# oresat0-plusz-end-cap.net
KiCad netlist of a schematic drawn in EAGLE
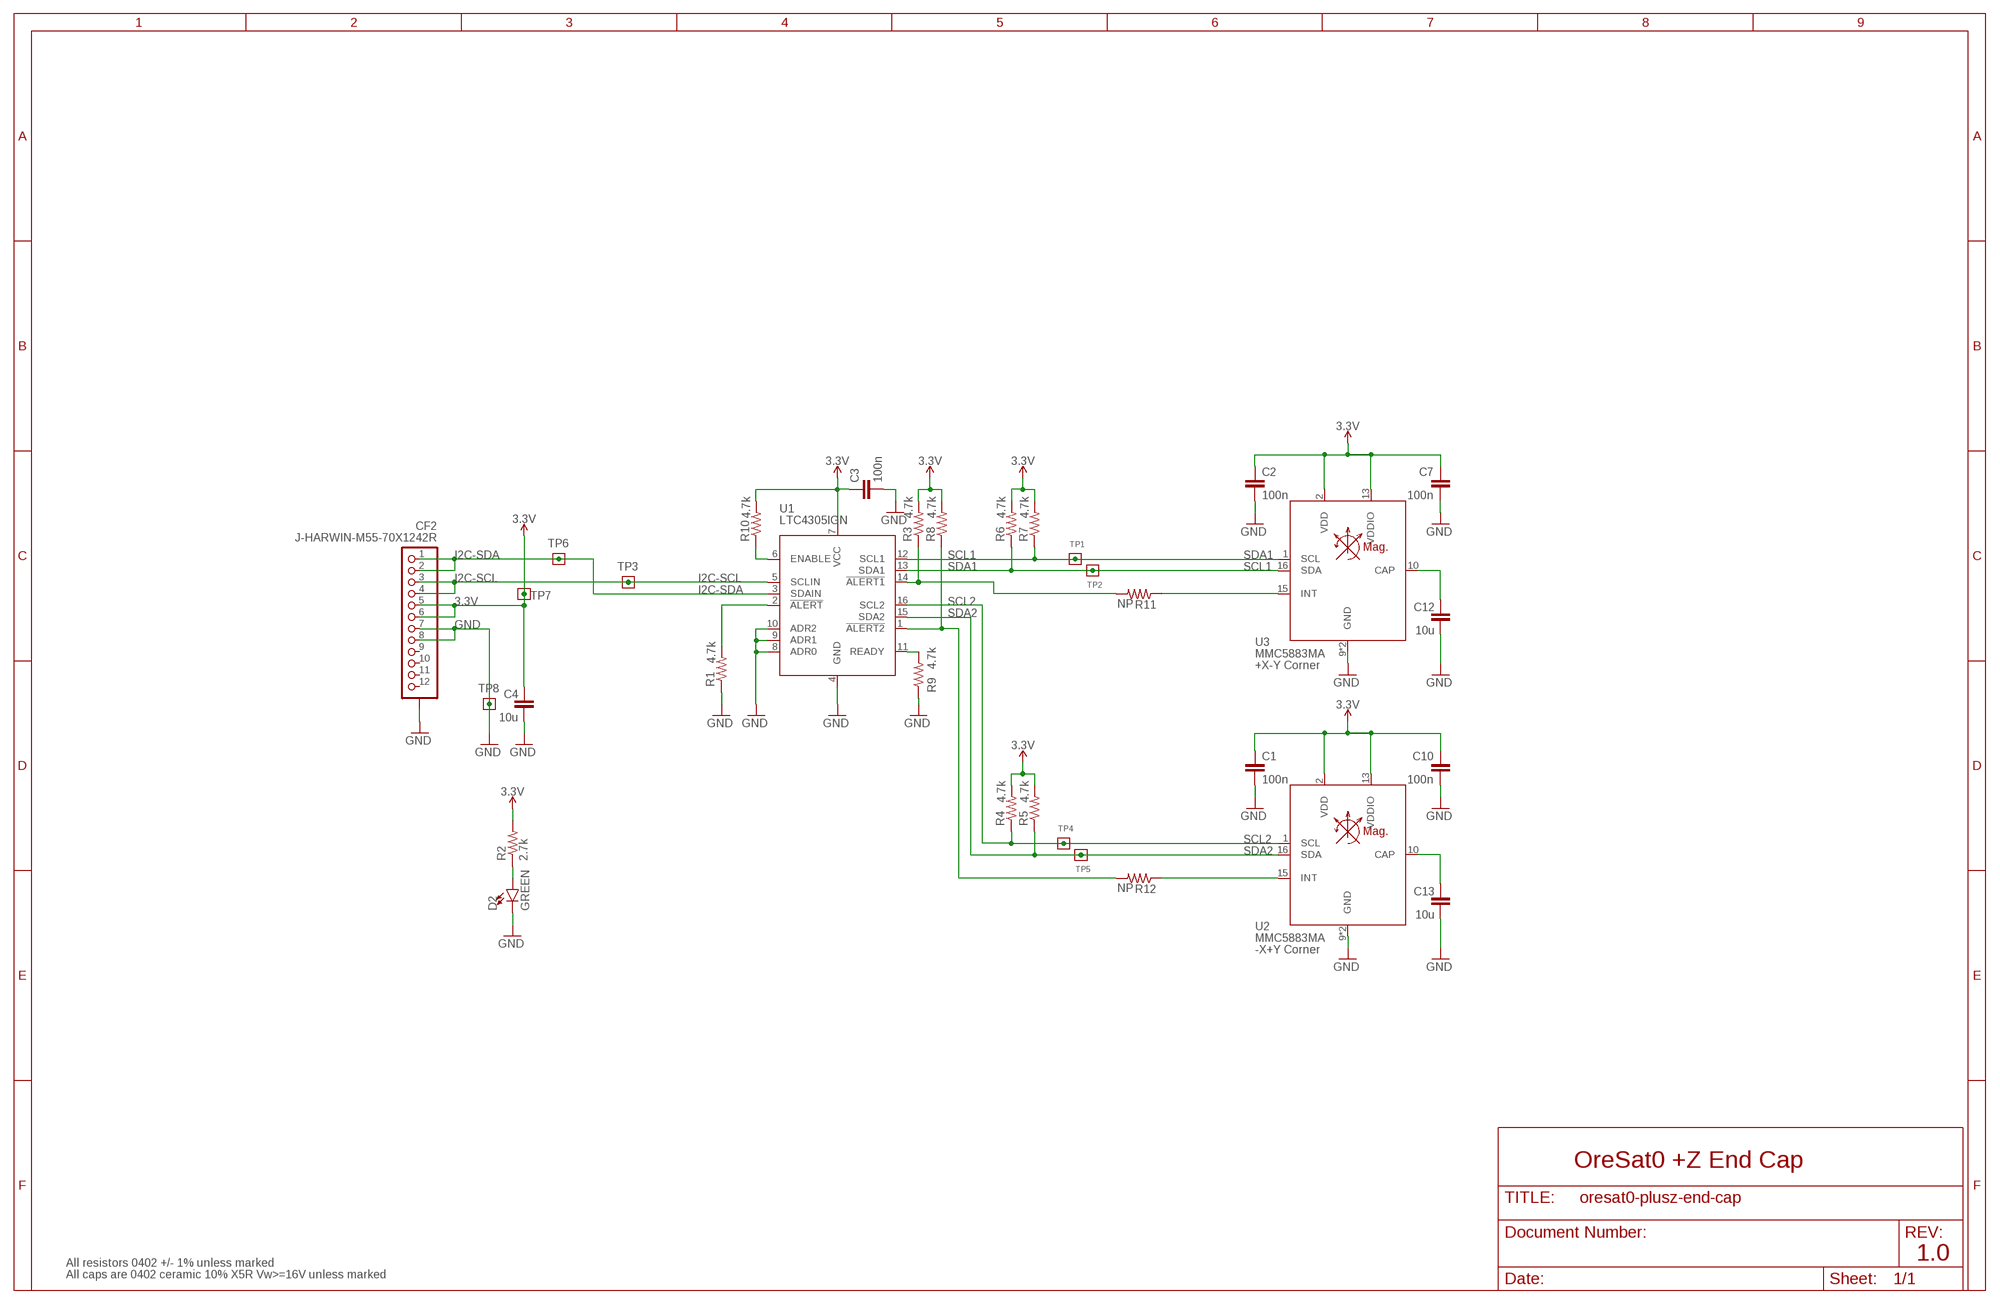
[diagram p0: schematic, sheet 1]

(export (version "E")
  (design (tool "Eeschema 10.0.6"))
  (components
    (comp (ref "C1")
      (value "100n")
      (footprint "eagle-import:.0603-B-NOSILK")
      (fields (field (name "MFR") "Samsung") (field (name "MPN") "CL10B104KB8NNNL"))
      (libsource (lib "eagle-import") (part "C-EU0603-B-NOSILK"))
    )
    (comp (ref "C2")
      (value "100n")
      (footprint "eagle-import:.0603-B-NOSILK")
      (fields (field (name "MFR") "Samsung") (field (name "MPN") "CL10B104KB8NNNL"))
      (libsource (lib "eagle-import") (part "C-EU0603-B-NOSILK"))
    )
    (comp (ref "C3")
      (value "100n")
      (footprint "eagle-import:.0603-B-NOSILK")
      (fields (field (name "MFR") "Samsung") (field (name "MPN") "CL10B104KB8NNNL"))
      (libsource (lib "eagle-import") (part "C-EU0603-B-NOSILK"))
    )
    (comp (ref "C4")
      (value "10u")
      (footprint "eagle-import:.0603-B-NOSILK")
      (fields (field (name "MFR") "Murata") (field (name "MPN") "GRM188D71A106KA73D"))
      (libsource (lib "eagle-import") (part "C-EU0603-B-NOSILK"))
    )
    (comp (ref "C7")
      (value "100n")
      (footprint "eagle-import:.0603-B-NOSILK")
      (fields (field (name "MFR") "Samsung") (field (name "MPN") "CL10B104KB8NNNL"))
      (libsource (lib "eagle-import") (part "C-EU0603-B-NOSILK"))
    )
    (comp (ref "C10")
      (value "100n")
      (footprint "eagle-import:.0603-B-NOSILK")
      (fields (field (name "MFR") "Samsung") (field (name "MPN") "CL10B104KB8NNNL"))
      (libsource (lib "eagle-import") (part "C-EU0603-B-NOSILK"))
    )
    (comp (ref "C12")
      (value "10u")
      (footprint "eagle-import:.0603-B-NOSILK")
      (fields (field (name "MFR") "Murata") (field (name "MPN") "GRM188D71A106KA73D"))
      (libsource (lib "eagle-import") (part "C-EU0603-B-NOSILK"))
    )
    (comp (ref "C13")
      (value "10u")
      (footprint "eagle-import:.0603-B-NOSILK")
      (fields (field (name "MFR") "Murata") (field (name "MPN") "GRM188D71A106KA73D"))
      (libsource (lib "eagle-import") (part "C-EU0603-B-NOSILK"))
    )
    (comp (ref "CF2")
      (value "J-HARWIN-M55-70X1242R")
      (footprint "eagle-import:HARWIN-M55-70X1242R")
      (fields (field (name "MFR") "Harwin") (field (name "MPN") "M55-7011242R"))
      (libsource (lib "eagle-import") (part "J-HARWIN-M55-70X1242R"))
    )
    (comp (ref "D2")
      (value "GREEN")
      (footprint "eagle-import:LED-0603")
      (fields (field (name "MFR") "Rohn") (field (name "MPN") "SML-E12M8WT86"))
      (libsource (lib "eagle-import") (part "LED-GREEN0603"))
    )
    (comp (ref "R1")
      (value "4.7k")
      (footprint "eagle-import:.0603-B-NOSILK")
      (fields (field (name "MFR") "TE Connectivity") (field (name "MPN") "CRGCQ0603F4K7"))
      (libsource (lib "eagle-import") (part "R-US_0603-B-NOSILK"))
    )
    (comp (ref "R2")
      (value "2.7k")
      (footprint "eagle-import:.0603-B-NOSILK")
      (fields (field (name "MFR") "TE Connectivity") (field (name "MPN") "CRGCQ0603F2K7"))
      (libsource (lib "eagle-import") (part "R-US_0603-B-NOSILK"))
    )
    (comp (ref "R3")
      (value "4.7k")
      (footprint "eagle-import:.0603-B-NOSILK")
      (fields (field (name "MFR") "TE Connectivity") (field (name "MPN") "CRGCQ0603F4K7"))
      (libsource (lib "eagle-import") (part "R-US_0603-B-NOSILK"))
    )
    (comp (ref "R4")
      (value "4.7k")
      (footprint "eagle-import:.0603-B-NOSILK")
      (fields (field (name "MFR") "TE Connectivity") (field (name "MPN") "CRGCQ0603F4K7"))
      (libsource (lib "eagle-import") (part "R-US_0603-B-NOSILK"))
    )
    (comp (ref "R5")
      (value "4.7k")
      (footprint "eagle-import:.0603-B-NOSILK")
      (fields (field (name "MFR") "TE Connectivity") (field (name "MPN") "CRGCQ0603F4K7"))
      (libsource (lib "eagle-import") (part "R-US_0603-B-NOSILK"))
    )
    (comp (ref "R6")
      (value "4.7k")
      (footprint "eagle-import:.0603-B-NOSILK")
      (fields (field (name "MFR") "TE Connectivity") (field (name "MPN") "CRGCQ0603F4K7"))
      (libsource (lib "eagle-import") (part "R-US_0603-B-NOSILK"))
    )
    (comp (ref "R7")
      (value "4.7k")
      (footprint "eagle-import:.0603-B-NOSILK")
      (fields (field (name "MFR") "TE Connectivity") (field (name "MPN") "CRGCQ0603F4K7"))
      (libsource (lib "eagle-import") (part "R-US_0603-B-NOSILK"))
    )
    (comp (ref "R8")
      (value "4.7k")
      (footprint "eagle-import:.0603-B-NOSILK")
      (fields (field (name "MFR") "TE Connectivity") (field (name "MPN") "CRGCQ0603F4K7"))
      (libsource (lib "eagle-import") (part "R-US_0603-B-NOSILK"))
    )
    (comp (ref "R9")
      (value "4.7k")
      (footprint "eagle-import:.0603-B-NOSILK")
      (fields (field (name "MFR") "TE Connectivity") (field (name "MPN") "CRGCQ0603F4K7"))
      (libsource (lib "eagle-import") (part "R-US_0603-B-NOSILK"))
    )
    (comp (ref "R10")
      (value "4.7k")
      (footprint "eagle-import:.0603-B-NOSILK")
      (fields (field (name "MFR") "TE Connectivity") (field (name "MPN") "CRGCQ0603F4K7"))
      (libsource (lib "eagle-import") (part "R-US_0603-B-NOSILK"))
    )
    (comp (ref "R11")
      (value "NP")
      (footprint "eagle-import:.0603-B-NOSILK")
      (libsource (lib "eagle-import") (part "R-US_0603-B-NOSILK"))
    )
    (comp (ref "R12")
      (value "NP")
      (footprint "eagle-import:.0603-B-NOSILK")
      (libsource (lib "eagle-import") (part "R-US_0603-B-NOSILK"))
    )
    (comp (ref "TP1")
      (value "TEST-POINT-LARGE-SQUARE")
      (footprint "eagle-import:1X01")
      (libsource (lib "eagle-import") (part "TEST-POINT-LARGE-SQUARE"))
    )
    (comp (ref "TP2")
      (value "TEST-POINT-LARGE-SQUARE")
      (footprint "eagle-import:1X01")
      (libsource (lib "eagle-import") (part "TEST-POINT-LARGE-SQUARE"))
    )
    (comp (ref "TP3")
      (value "TEST-POINT-LARGE-SQUARE")
      (footprint "eagle-import:1X01")
      (libsource (lib "eagle-import") (part "TEST-POINT-LARGE-SQUARE"))
    )
    (comp (ref "TP4")
      (value "TEST-POINT-LARGE-SQUARE")
      (footprint "eagle-import:1X01")
      (libsource (lib "eagle-import") (part "TEST-POINT-LARGE-SQUARE"))
    )
    (comp (ref "TP5")
      (value "TEST-POINT-LARGE-SQUARE")
      (footprint "eagle-import:1X01")
      (libsource (lib "eagle-import") (part "TEST-POINT-LARGE-SQUARE"))
    )
    (comp (ref "TP6")
      (value "TEST-POINT-LARGE-SQUARE")
      (footprint "eagle-import:1X01")
      (libsource (lib "eagle-import") (part "TEST-POINT-LARGE-SQUARE"))
    )
    (comp (ref "TP7")
      (value "TEST-POINT-LARGE-SQUARE")
      (footprint "eagle-import:1X01")
      (libsource (lib "eagle-import") (part "TEST-POINT-LARGE-SQUARE"))
    )
    (comp (ref "TP8")
      (value "TEST-POINT-LARGE-SQUARE")
      (footprint "eagle-import:1X01")
      (libsource (lib "eagle-import") (part "TEST-POINT-LARGE-SQUARE"))
    )
    (comp (ref "U1")
      (value "LTC4305IGN")
      (footprint "eagle-import:16-SSOP")
      (fields (field (name "MFR") "Analog") (field (name "MPN") "LTC4305IGN#PBF"))
      (libsource (lib "eagle-import") (part "LTC4305"))
    )
    (comp (ref "U2")
      (value "MMC5883MA")
      (footprint "eagle-import:LGA-16(3X3)")
      (fields (field (name "MFR") "Memsic"))
      (libsource (lib "eagle-import") (part "MMC5883MA"))
    )
    (comp (ref "U3")
      (value "MMC5883MA")
      (footprint "eagle-import:LGA-16(3X3)")
      (fields (field (name "MFR") "Memsic"))
      (libsource (lib "eagle-import") (part "MMC5883MA"))
    )
  )
  (nets
    (net (code "1") (name "/I2C-SCL") (class "Default")
      (node (ref "CF2") (pin "3") (pinfunction "3_3") (pintype "passive"))
      (node (ref "CF2") (pin "4") (pinfunction "4_4") (pintype "passive"))
      (node (ref "TP3") (pin "1") (pinfunction "1_1") (pintype "passive"))
      (node (ref "U1") (pin "5") (pinfunction "SCLIN_5") (pintype "bidirectional"))
    )
    (net (code "2") (name "/I2C-SDA") (class "Default")
      (node (ref "CF2") (pin "1") (pinfunction "1_1") (pintype "passive"))
      (node (ref "CF2") (pin "2") (pinfunction "2_2") (pintype "passive"))
      (node (ref "TP6") (pin "1") (pinfunction "1_1") (pintype "passive"))
      (node (ref "U1") (pin "3") (pinfunction "SDAIN_3") (pintype "bidirectional"))
    )
    (net (code "3") (name "/SCL1") (class "Default")
      (node (ref "R7") (pin "1") (pinfunction "1_1") (pintype "passive"))
      (node (ref "TP1") (pin "1") (pinfunction "1_1") (pintype "passive"))
      (node (ref "U1") (pin "12") (pinfunction "SCL1_12") (pintype "bidirectional"))
      (node (ref "U3") (pin "1") (pinfunction "SCL_1") (pintype "input"))
    )
    (net (code "4") (name "/SCL2") (class "Default")
      (node (ref "R4") (pin "1") (pinfunction "1_1") (pintype "passive"))
      (node (ref "TP4") (pin "1") (pinfunction "1_1") (pintype "passive"))
      (node (ref "U1") (pin "16") (pinfunction "SCL2_16") (pintype "bidirectional"))
      (node (ref "U2") (pin "1") (pinfunction "SCL_1") (pintype "input"))
    )
    (net (code "5") (name "/SDA1") (class "Default")
      (node (ref "R6") (pin "1") (pinfunction "1_1") (pintype "passive"))
      (node (ref "TP2") (pin "1") (pinfunction "1_1") (pintype "passive"))
      (node (ref "U1") (pin "13") (pinfunction "SDA1_13") (pintype "bidirectional"))
      (node (ref "U3") (pin "16") (pinfunction "SDA_16") (pintype "bidirectional"))
    )
    (net (code "6") (name "/SDA2") (class "Default")
      (node (ref "R5") (pin "1") (pinfunction "1_1") (pintype "passive"))
      (node (ref "TP5") (pin "1") (pinfunction "1_1") (pintype "passive"))
      (node (ref "U1") (pin "15") (pinfunction "SDA2_15") (pintype "bidirectional"))
      (node (ref "U2") (pin "16") (pinfunction "SDA_16") (pintype "bidirectional"))
    )
    (net (code "7") (name "3.3V") (class "Default")
      (node (ref "C1") (pin "1") (pinfunction "1_1") (pintype "passive"))
      (node (ref "C10") (pin "1") (pinfunction "1_1") (pintype "passive"))
      (node (ref "C2") (pin "1") (pinfunction "1_1") (pintype "passive"))
      (node (ref "C3") (pin "1") (pinfunction "1_1") (pintype "passive"))
      (node (ref "C4") (pin "1") (pinfunction "1_1") (pintype "passive"))
      (node (ref "C7") (pin "1") (pinfunction "1_1") (pintype "passive"))
      (node (ref "CF2") (pin "5") (pinfunction "5_5") (pintype "passive"))
      (node (ref "CF2") (pin "6") (pinfunction "6_6") (pintype "passive"))
      (node (ref "R10") (pin "2") (pinfunction "2_2") (pintype "passive"))
      (node (ref "R2") (pin "2") (pinfunction "2_2") (pintype "passive"))
      (node (ref "R3") (pin "2") (pinfunction "2_2") (pintype "passive"))
      (node (ref "R4") (pin "2") (pinfunction "2_2") (pintype "passive"))
      (node (ref "R5") (pin "2") (pinfunction "2_2") (pintype "passive"))
      (node (ref "R6") (pin "2") (pinfunction "2_2") (pintype "passive"))
      (node (ref "R7") (pin "2") (pinfunction "2_2") (pintype "passive"))
      (node (ref "R8") (pin "2") (pinfunction "2_2") (pintype "passive"))
      (node (ref "TP7") (pin "1") (pinfunction "1_1") (pintype "passive"))
      (node (ref "U1") (pin "7") (pinfunction "VCC_7") (pintype "power_in"))
      (node (ref "U2") (pin "13") (pinfunction "VDDIO_13") (pintype "power_in"))
      (node (ref "U2") (pin "2") (pinfunction "VDD_2") (pintype "power_in"))
      (node (ref "U3") (pin "13") (pinfunction "VDDIO_13") (pintype "power_in"))
      (node (ref "U3") (pin "2") (pinfunction "VDD_2") (pintype "power_in"))
    )
    (net (code "8") (name "GND") (class "Default")
      (node (ref "C1") (pin "2") (pinfunction "2_2") (pintype "passive"))
      (node (ref "C10") (pin "2") (pinfunction "2_2") (pintype "passive"))
      (node (ref "C12") (pin "2") (pinfunction "2_2") (pintype "passive"))
      (node (ref "C13") (pin "2") (pinfunction "2_2") (pintype "passive"))
      (node (ref "C2") (pin "2") (pinfunction "2_2") (pintype "passive"))
      (node (ref "C3") (pin "2") (pinfunction "2_2") (pintype "passive"))
      (node (ref "C4") (pin "2") (pinfunction "2_2") (pintype "passive"))
      (node (ref "C7") (pin "2") (pinfunction "2_2") (pintype "passive"))
      (node (ref "CF2") (pin "7") (pinfunction "7_7") (pintype "passive"))
      (node (ref "CF2") (pin "8") (pinfunction "8_8") (pintype "passive"))
      (node (ref "CF2") (pin "P$1") (pinfunction "SHIELDS_P$1") (pintype "passive"))
      (node (ref "CF2") (pin "P$2") (pinfunction "SHIELDS_P$2") (pintype "passive"))
      (node (ref "CF2") (pin "P$3") (pinfunction "SHIELDS_P$3") (pintype "passive"))
      (node (ref "CF2") (pin "P$4") (pinfunction "SHIELDS_P$4") (pintype "passive"))
      (node (ref "D2") (pin "C") (pinfunction "C_C") (pintype "passive"))
      (node (ref "R1") (pin "1") (pinfunction "1_1") (pintype "passive"))
      (node (ref "R9") (pin "1") (pinfunction "1_1") (pintype "passive"))
      (node (ref "TP8") (pin "1") (pinfunction "1_1") (pintype "passive"))
      (node (ref "U1") (pin "10") (pinfunction "ADR2_10") (pintype "input"))
      (node (ref "U1") (pin "4") (pinfunction "GND_4") (pintype "power_in"))
      (node (ref "U1") (pin "8") (pinfunction "ADR0_8") (pintype "input"))
      (node (ref "U1") (pin "9") (pinfunction "ADR1_9") (pintype "input"))
      (node (ref "U2") (pin "11") (pinfunction "GND_11") (pintype "power_in"))
      (node (ref "U2") (pin "9") (pinfunction "GND_9") (pintype "power_in"))
      (node (ref "U3") (pin "11") (pinfunction "GND_11") (pintype "power_in"))
      (node (ref "U3") (pin "9") (pinfunction "GND_9") (pintype "power_in"))
    )
    (net (code "9") (name "Net-(D2-PadA)") (class "Default")
      (node (ref "D2") (pin "A") (pinfunction "A_A") (pintype "passive"))
      (node (ref "R2") (pin "1") (pinfunction "1_1") (pintype "passive"))
    )
    (net (code "10") (name "Net-(U1-ENABLE)") (class "Default")
      (node (ref "R10") (pin "1") (pinfunction "1_1") (pintype "passive"))
      (node (ref "U1") (pin "6") (pinfunction "ENABLE_6") (pintype "input"))
    )
    (net (code "11") (name "Net-(U1-READY)") (class "Default")
      (node (ref "R9") (pin "2") (pinfunction "2_2") (pintype "passive"))
      (node (ref "U1") (pin "11") (pinfunction "READY_11") (pintype "output"))
    )
    (net (code "12") (name "Net-(U1-~{ALERT1})") (class "Default")
      (node (ref "R11") (pin "2") (pinfunction "2_2") (pintype "passive"))
      (node (ref "R3") (pin "1") (pinfunction "1_1") (pintype "passive"))
      (node (ref "U1") (pin "14") (pinfunction "~{ALERT1}_14") (pintype "input"))
    )
    (net (code "13") (name "Net-(U1-~{ALERT2})") (class "Default")
      (node (ref "R12") (pin "2") (pinfunction "2_2") (pintype "passive"))
      (node (ref "R8") (pin "1") (pinfunction "1_1") (pintype "passive"))
      (node (ref "U1") (pin "1") (pinfunction "~{ALERT2}_1") (pintype "input"))
    )
    (net (code "14") (name "Net-(U1-~{ALERT})") (class "Default")
      (node (ref "R1") (pin "2") (pinfunction "2_2") (pintype "passive"))
      (node (ref "U1") (pin "2") (pinfunction "~{ALERT}_2") (pintype "output"))
    )
    (net (code "15") (name "Net-(U2-CAP)") (class "Default")
      (node (ref "C13") (pin "1") (pinfunction "1_1") (pintype "passive"))
      (node (ref "U2") (pin "10") (pinfunction "CAP_10") (pintype "power_in"))
    )
    (net (code "16") (name "Net-(U2-INT)") (class "Default")
      (node (ref "R12") (pin "1") (pinfunction "1_1") (pintype "passive"))
      (node (ref "U2") (pin "15") (pinfunction "INT_15") (pintype "output"))
    )
    (net (code "17") (name "Net-(U3-CAP)") (class "Default")
      (node (ref "C12") (pin "1") (pinfunction "1_1") (pintype "passive"))
      (node (ref "U3") (pin "10") (pinfunction "CAP_10") (pintype "power_in"))
    )
    (net (code "18") (name "Net-(U3-INT)") (class "Default")
      (node (ref "R11") (pin "1") (pinfunction "1_1") (pintype "passive"))
      (node (ref "U3") (pin "15") (pinfunction "INT_15") (pintype "output"))
    )
    (net (code "19") (name "unconnected-(CF2-Pad9)") (class "Default")
      (node (ref "CF2") (pin "9") (pinfunction "9_9") (pintype "passive"))
    )
    (net (code "20") (name "unconnected-(CF2-Pad10)") (class "Default")
      (node (ref "CF2") (pin "10") (pinfunction "10_10") (pintype "passive"))
    )
    (net (code "21") (name "unconnected-(CF2-Pad11)") (class "Default")
      (node (ref "CF2") (pin "11") (pinfunction "11_11") (pintype "passive"))
    )
    (net (code "22") (name "unconnected-(CF2-Pad12)") (class "Default")
      (node (ref "CF2") (pin "12") (pinfunction "12_12") (pintype "passive"))
    )
  )
)
